# lm324am_voltage.net
KiCad netlist of a schematic drawn in EAGLE
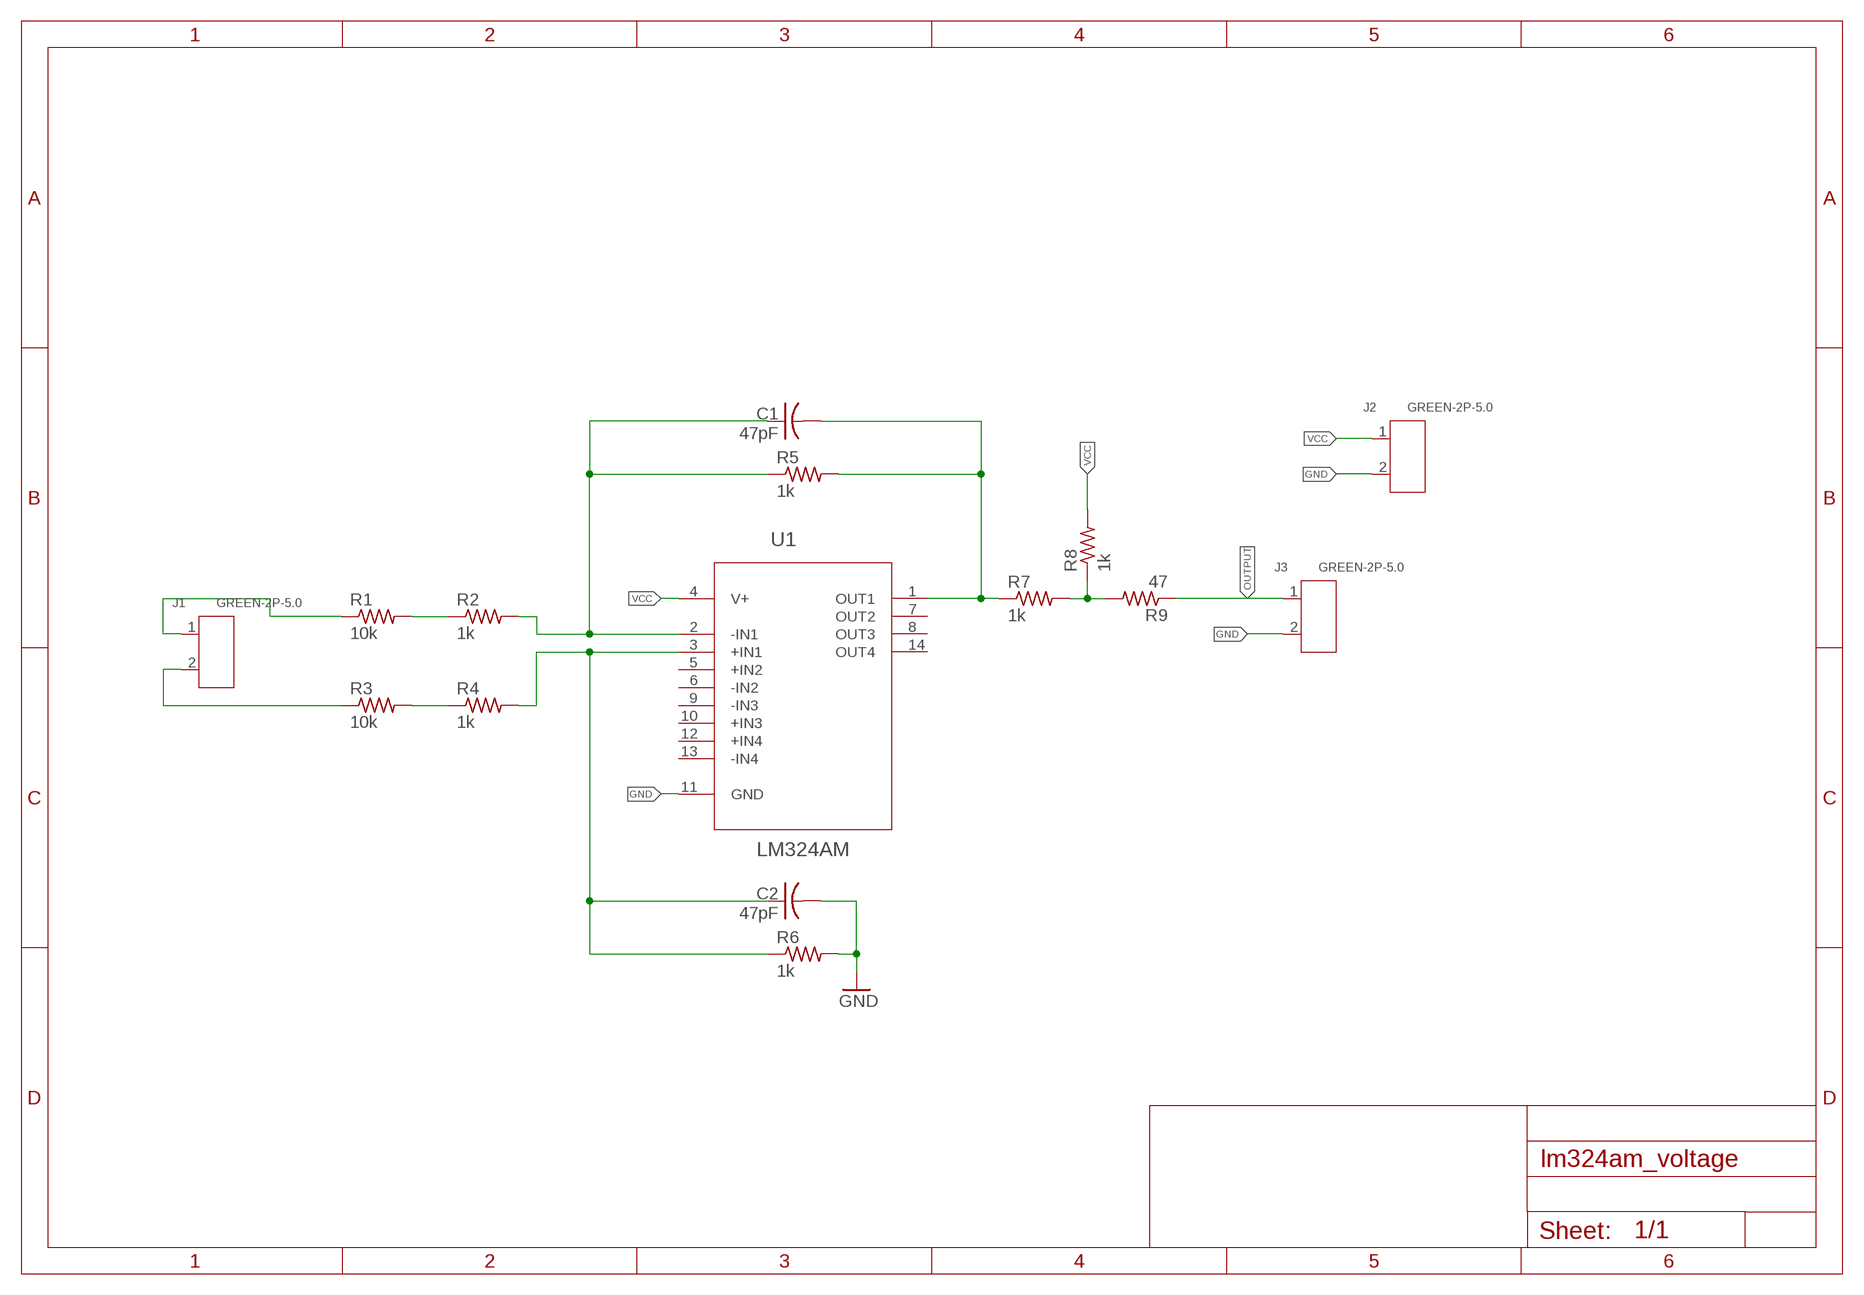
[diagram p0: schematic, sheet 1]

(export (version "E")
  (design (tool "Eeschema 10.0.6"))
  (components
    (comp (ref "C1")
      (value "47pF")
      (footprint "eagle-import:C1206")
      (libsource (lib "eagle-import") (part "C-USC1206"))
    )
    (comp (ref "C2")
      (value "47pF")
      (footprint "eagle-import:C1206")
      (libsource (lib "eagle-import") (part "C-USC1206"))
    )
    (comp (ref "J1")
      (value "GREEN-2P-5.0")
      (footprint "eagle-import:H2-5.0-10.5X8.0MM")
      (libsource (lib "eagle-import") (part "SCREW-TERMINAL-GREEN(2P-5.0)"))
    )
    (comp (ref "J2")
      (value "GREEN-2P-5.0")
      (footprint "eagle-import:H2-5.0-10.5X8.0MM")
      (libsource (lib "eagle-import") (part "SCREW-TERMINAL-GREEN(2P-5.0)"))
    )
    (comp (ref "J3")
      (value "GREEN-2P-5.0")
      (footprint "eagle-import:H2-5.0-10.5X8.0MM")
      (libsource (lib "eagle-import") (part "SCREW-TERMINAL-GREEN(2P-5.0)"))
    )
    (comp (ref "R1")
      (value "10k")
      (footprint "eagle-import:M1206")
      (libsource (lib "eagle-import") (part "R-US_M1206"))
    )
    (comp (ref "R2")
      (value "1k")
      (footprint "eagle-import:M1206")
      (libsource (lib "eagle-import") (part "R-US_M1206"))
    )
    (comp (ref "R3")
      (value "10k")
      (footprint "eagle-import:M1206")
      (libsource (lib "eagle-import") (part "R-US_M1206"))
    )
    (comp (ref "R4")
      (value "1k")
      (footprint "eagle-import:M1206")
      (libsource (lib "eagle-import") (part "R-US_M1206"))
    )
    (comp (ref "R5")
      (value "1k")
      (footprint "eagle-import:M1206")
      (libsource (lib "eagle-import") (part "R-US_M1206"))
    )
    (comp (ref "R6")
      (value "1k")
      (footprint "eagle-import:M1206")
      (libsource (lib "eagle-import") (part "R-US_M1206"))
    )
    (comp (ref "R7")
      (value "1k")
      (footprint "eagle-import:M1206")
      (libsource (lib "eagle-import") (part "R-US_M1206"))
    )
    (comp (ref "R8")
      (value "1k")
      (footprint "eagle-import:M1206")
      (libsource (lib "eagle-import") (part "R-US_M1206"))
    )
    (comp (ref "R9")
      (value "47")
      (footprint "eagle-import:M1206")
      (libsource (lib "eagle-import") (part "R-US_M1206"))
    )
    (comp (ref "U1")
      (value "LM324AM")
      (footprint "eagle-import:SOIC127P620X175-14N")
      (fields (field (name "MF") "Texas Instruments"))
      (libsource (lib "eagle-import") (part "LM324AM"))
    )
  )
  (nets
    (net (code "1") (name "GND") (class "Default")
      (node (ref "C2") (pin "2") (pinfunction "2_2") (pintype "passive"))
      (node (ref "J2") (pin "2") (pinfunction "2_2") (pintype "bidirectional"))
      (node (ref "J3") (pin "2") (pinfunction "2_2") (pintype "bidirectional"))
      (node (ref "R6") (pin "2") (pinfunction "2_2") (pintype "passive"))
      (node (ref "U1") (pin "11") (pinfunction "GND_11") (pintype "passive"))
    )
    (net (code "2") (name "Net-(J1-Pad1)") (class "Default")
      (node (ref "J1") (pin "1") (pinfunction "1_1") (pintype "bidirectional"))
      (node (ref "R1") (pin "1") (pinfunction "1_1") (pintype "passive"))
    )
    (net (code "3") (name "Net-(J1-Pad2)") (class "Default")
      (node (ref "J1") (pin "2") (pinfunction "2_2") (pintype "bidirectional"))
      (node (ref "R3") (pin "1") (pinfunction "1_1") (pintype "passive"))
    )
    (net (code "4") (name "Net-(R1-Pad2)") (class "Default")
      (node (ref "R1") (pin "2") (pinfunction "2_2") (pintype "passive"))
      (node (ref "R2") (pin "1") (pinfunction "1_1") (pintype "passive"))
    )
    (net (code "5") (name "Net-(R3-Pad2)") (class "Default")
      (node (ref "R3") (pin "2") (pinfunction "2_2") (pintype "passive"))
      (node (ref "R4") (pin "1") (pinfunction "1_1") (pintype "passive"))
    )
    (net (code "6") (name "Net-(R7-Pad2)") (class "Default")
      (node (ref "R7") (pin "2") (pinfunction "2_2") (pintype "passive"))
      (node (ref "R8") (pin "1") (pinfunction "1_1") (pintype "passive"))
      (node (ref "R9") (pin "2") (pinfunction "2_2") (pintype "passive"))
    )
    (net (code "7") (name "Net-(U1-+IN1)") (class "Default")
      (node (ref "C2") (pin "1") (pinfunction "1_1") (pintype "passive"))
      (node (ref "R4") (pin "2") (pinfunction "2_2") (pintype "passive"))
      (node (ref "R6") (pin "1") (pinfunction "1_1") (pintype "passive"))
      (node (ref "U1") (pin "3") (pinfunction "+IN1_3") (pintype "input"))
    )
    (net (code "8") (name "Net-(U1--IN1)") (class "Default")
      (node (ref "C1") (pin "1") (pinfunction "1_1") (pintype "passive"))
      (node (ref "R2") (pin "2") (pinfunction "2_2") (pintype "passive"))
      (node (ref "R5") (pin "1") (pinfunction "1_1") (pintype "passive"))
      (node (ref "U1") (pin "2") (pinfunction "-IN1_2") (pintype "input"))
    )
    (net (code "9") (name "Net-(U1-OUT1)") (class "Default")
      (node (ref "C1") (pin "2") (pinfunction "2_2") (pintype "passive"))
      (node (ref "R5") (pin "2") (pinfunction "2_2") (pintype "passive"))
      (node (ref "R7") (pin "1") (pinfunction "1_1") (pintype "passive"))
      (node (ref "U1") (pin "1") (pinfunction "OUT1_1") (pintype "output"))
    )
    (net (code "10") (name "OUTPUT") (class "Default")
      (node (ref "J3") (pin "1") (pinfunction "1_1") (pintype "bidirectional"))
      (node (ref "R9") (pin "1") (pinfunction "1_1") (pintype "passive"))
    )
    (net (code "11") (name "VCC") (class "Default")
      (node (ref "J2") (pin "1") (pinfunction "1_1") (pintype "bidirectional"))
      (node (ref "R8") (pin "2") (pinfunction "2_2") (pintype "passive"))
      (node (ref "U1") (pin "4") (pinfunction "V+_4") (pintype "power_in"))
    )
    (net (code "12") (name "unconnected-(U1-+IN2-Pad5)") (class "Default")
      (node (ref "U1") (pin "5") (pinfunction "+IN2_5") (pintype "input"))
    )
    (net (code "13") (name "unconnected-(U1-+IN3-Pad10)") (class "Default")
      (node (ref "U1") (pin "10") (pinfunction "+IN3_10") (pintype "input"))
    )
    (net (code "14") (name "unconnected-(U1-+IN4-Pad12)") (class "Default")
      (node (ref "U1") (pin "12") (pinfunction "+IN4_12") (pintype "input"))
    )
    (net (code "15") (name "unconnected-(U1--IN2-Pad6)") (class "Default")
      (node (ref "U1") (pin "6") (pinfunction "-IN2_6") (pintype "input"))
    )
    (net (code "16") (name "unconnected-(U1--IN3-Pad9)") (class "Default")
      (node (ref "U1") (pin "9") (pinfunction "-IN3_9") (pintype "input"))
    )
    (net (code "17") (name "unconnected-(U1--IN4-Pad13)") (class "Default")
      (node (ref "U1") (pin "13") (pinfunction "-IN4_13") (pintype "input"))
    )
    (net (code "18") (name "unconnected-(U1-OUT2-Pad7)") (class "Default")
      (node (ref "U1") (pin "7") (pinfunction "OUT2_7") (pintype "output"))
    )
    (net (code "19") (name "unconnected-(U1-OUT3-Pad8)") (class "Default")
      (node (ref "U1") (pin "8") (pinfunction "OUT3_8") (pintype "output"))
    )
    (net (code "20") (name "unconnected-(U1-OUT4-Pad14)") (class "Default")
      (node (ref "U1") (pin "14") (pinfunction "OUT4_14") (pintype "output"))
    )
  )
)
